# Esp32.net
KiCad netlist of a schematic drawn in Altium Designer
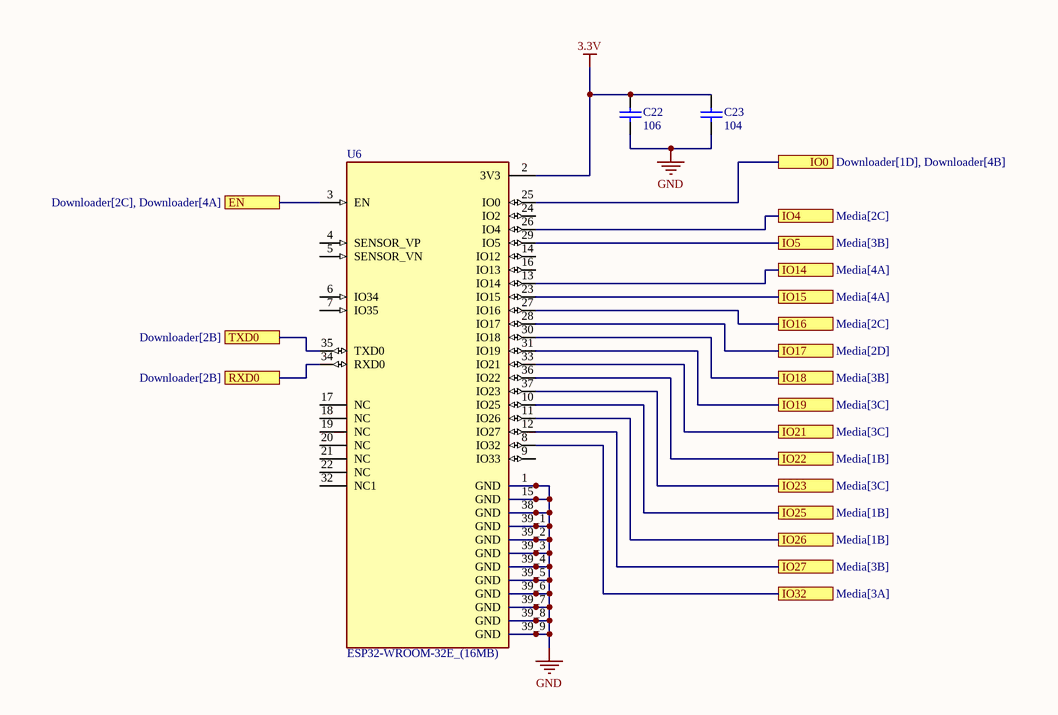
[diagram p0: Esp32.SchDoc]

(export (version "E")
  (design (tool "Eeschema 10.0.6"))
  (components
    (comp (ref "C22")
      (value "106")
      (footprint "tu 0805")
      (description "Dán")
      (libsource (lib "Altium_Lib_by_KhueNguyenCreator") (part "Tu 0805 106 16V 10%"))
    )
    (comp (ref "C23")
      (value "104")
      (footprint "tu 0805")
      (description "Dán")
      (libsource (lib "Altium_Lib_by_KhueNguyenCreator") (part "Tu 0805 106 16V 10%"))
    )
    (comp (ref "U6")
      (value "ESP32-WROOM-32E_(16MB)")
      (footprint "XCVR_ESP32-WROOM-32E_(16MB)")
      (fields (field (name "MP") "ESP32-WROOM-32E (16MB)") (field (name "MF") "Espressif Systems"))
      (libsource (lib "ESP32-WROOM-32E__16MB_") (part "ESP32-WROOM-32E_(16MB)"))
    )
  )
  (nets
    (net (code "1") (name "/EN") (class "Default")
      (node (ref "U6") (pin "3") (pinfunction "EN_3") (pintype "input"))
    )
    (net (code "2") (name "/IO0") (class "Default")
      (node (ref "U6") (pin "25") (pinfunction "IO0_25") (pintype "bidirectional"))
    )
    (net (code "3") (name "/IO4") (class "Default")
      (node (ref "U6") (pin "26") (pinfunction "IO4_26") (pintype "bidirectional"))
    )
    (net (code "4") (name "/IO5") (class "Default")
      (node (ref "U6") (pin "29") (pinfunction "IO5_29") (pintype "bidirectional"))
    )
    (net (code "5") (name "/IO14") (class "Default")
      (node (ref "U6") (pin "13") (pinfunction "IO14_13") (pintype "bidirectional"))
    )
    (net (code "6") (name "/IO15") (class "Default")
      (node (ref "U6") (pin "23") (pinfunction "IO15_23") (pintype "bidirectional"))
    )
    (net (code "7") (name "/IO16") (class "Default")
      (node (ref "U6") (pin "27") (pinfunction "IO16_27") (pintype "bidirectional"))
    )
    (net (code "8") (name "/IO17") (class "Default")
      (node (ref "U6") (pin "28") (pinfunction "IO17_28") (pintype "bidirectional"))
    )
    (net (code "9") (name "/IO18") (class "Default")
      (node (ref "U6") (pin "30") (pinfunction "IO18_30") (pintype "bidirectional"))
    )
    (net (code "10") (name "/IO19") (class "Default")
      (node (ref "U6") (pin "31") (pinfunction "IO19_31") (pintype "bidirectional"))
    )
    (net (code "11") (name "/IO21") (class "Default")
      (node (ref "U6") (pin "33") (pinfunction "IO21_33") (pintype "bidirectional"))
    )
    (net (code "12") (name "/IO22") (class "Default")
      (node (ref "U6") (pin "36") (pinfunction "IO22_36") (pintype "bidirectional"))
    )
    (net (code "13") (name "/IO23") (class "Default")
      (node (ref "U6") (pin "37") (pinfunction "IO23_37") (pintype "bidirectional"))
    )
    (net (code "14") (name "/IO25") (class "Default")
      (node (ref "U6") (pin "10") (pinfunction "IO25_10") (pintype "bidirectional"))
    )
    (net (code "15") (name "/IO26") (class "Default")
      (node (ref "U6") (pin "11") (pinfunction "IO26_11") (pintype "bidirectional"))
    )
    (net (code "16") (name "/IO27") (class "Default")
      (node (ref "U6") (pin "12") (pinfunction "IO27_12") (pintype "bidirectional"))
    )
    (net (code "17") (name "/IO32") (class "Default")
      (node (ref "U6") (pin "8") (pinfunction "IO32_8") (pintype "bidirectional"))
    )
    (net (code "18") (name "/RXD0") (class "Default")
      (node (ref "U6") (pin "34") (pinfunction "RXD0_34") (pintype "bidirectional"))
    )
    (net (code "19") (name "/TXD0") (class "Default")
      (node (ref "U6") (pin "35") (pinfunction "TXD0_35") (pintype "bidirectional"))
    )
    (net (code "20") (name "3.3V") (class "Default")
      (node (ref "C22") (pin "1") (pinfunction "1_1") (pintype "passive"))
      (node (ref "C23") (pin "1") (pinfunction "1_1") (pintype "passive"))
      (node (ref "U6") (pin "2") (pinfunction "3V3_2") (pintype "power_in"))
    )
    (net (code "21") (name "GND") (class "Default")
      (node (ref "C22") (pin "2") (pinfunction "2_2") (pintype "passive"))
      (node (ref "C23") (pin "2") (pinfunction "2_2") (pintype "passive"))
      (node (ref "U6") (pin "1") (pinfunction "GND_1") (pintype "power_in"))
      (node (ref "U6") (pin "15") (pinfunction "GND_15") (pintype "power_in"))
      (node (ref "U6") (pin "38") (pinfunction "GND_38") (pintype "power_in"))
      (node (ref "U6") (pin "39_1") (pinfunction "GND_39_1") (pintype "power_in"))
      (node (ref "U6") (pin "39_2") (pinfunction "GND_39_2") (pintype "power_in"))
      (node (ref "U6") (pin "39_3") (pinfunction "GND_39_3") (pintype "power_in"))
      (node (ref "U6") (pin "39_4") (pinfunction "GND_39_4") (pintype "power_in"))
      (node (ref "U6") (pin "39_5") (pinfunction "GND_39_5") (pintype "power_in"))
      (node (ref "U6") (pin "39_6") (pinfunction "GND_39_6") (pintype "power_in"))
      (node (ref "U6") (pin "39_7") (pinfunction "GND_39_7") (pintype "power_in"))
      (node (ref "U6") (pin "39_8") (pinfunction "GND_39_8") (pintype "power_in"))
      (node (ref "U6") (pin "39_9") (pinfunction "GND_39_9") (pintype "power_in"))
    )
    (net (code "22") (name "unconnected-(U6-IO2-Pad24)") (class "Default")
      (node (ref "U6") (pin "24") (pinfunction "IO2_24") (pintype "bidirectional"))
    )
    (net (code "23") (name "unconnected-(U6-IO12-Pad14)") (class "Default")
      (node (ref "U6") (pin "14") (pinfunction "IO12_14") (pintype "bidirectional"))
    )
    (net (code "24") (name "unconnected-(U6-IO13-Pad16)") (class "Default")
      (node (ref "U6") (pin "16") (pinfunction "IO13_16") (pintype "bidirectional"))
    )
    (net (code "25") (name "unconnected-(U6-IO33-Pad9)") (class "Default")
      (node (ref "U6") (pin "9") (pinfunction "IO33_9") (pintype "bidirectional"))
    )
    (net (code "26") (name "unconnected-(U6-IO34-Pad6)") (class "Default")
      (node (ref "U6") (pin "6") (pinfunction "IO34_6") (pintype "input"))
    )
    (net (code "27") (name "unconnected-(U6-IO35-Pad7)") (class "Default")
      (node (ref "U6") (pin "7") (pinfunction "IO35_7") (pintype "input"))
    )
    (net (code "28") (name "unconnected-(U6-NC-Pad17)") (class "Default")
      (node (ref "U6") (pin "17") (pinfunction "NC_17") (pintype "passive"))
    )
    (net (code "29") (name "unconnected-(U6-NC-Pad18)") (class "Default")
      (node (ref "U6") (pin "18") (pinfunction "NC_18") (pintype "passive"))
    )
    (net (code "30") (name "unconnected-(U6-NC-Pad19)") (class "Default")
      (node (ref "U6") (pin "19") (pinfunction "NC_19") (pintype "passive"))
    )
    (net (code "31") (name "unconnected-(U6-NC-Pad20)") (class "Default")
      (node (ref "U6") (pin "20") (pinfunction "NC_20") (pintype "passive"))
    )
    (net (code "32") (name "unconnected-(U6-NC-Pad21)") (class "Default")
      (node (ref "U6") (pin "21") (pinfunction "NC_21") (pintype "passive"))
    )
    (net (code "33") (name "unconnected-(U6-NC-Pad22)") (class "Default")
      (node (ref "U6") (pin "22") (pinfunction "NC_22") (pintype "passive"))
    )
    (net (code "34") (name "unconnected-(U6-NC1-Pad32)") (class "Default")
      (node (ref "U6") (pin "32") (pinfunction "NC1_32") (pintype "passive"))
    )
    (net (code "35") (name "unconnected-(U6-SENSOR_VN-Pad5)") (class "Default")
      (node (ref "U6") (pin "5") (pinfunction "SENSOR_VN_5") (pintype "input"))
    )
    (net (code "36") (name "unconnected-(U6-SENSOR_VP-Pad4)") (class "Default")
      (node (ref "U6") (pin "4") (pinfunction "SENSOR_VP_4") (pintype "input"))
    )
  )
)
